# shield.net
KiCad netlist of a schematic drawn in EAGLE
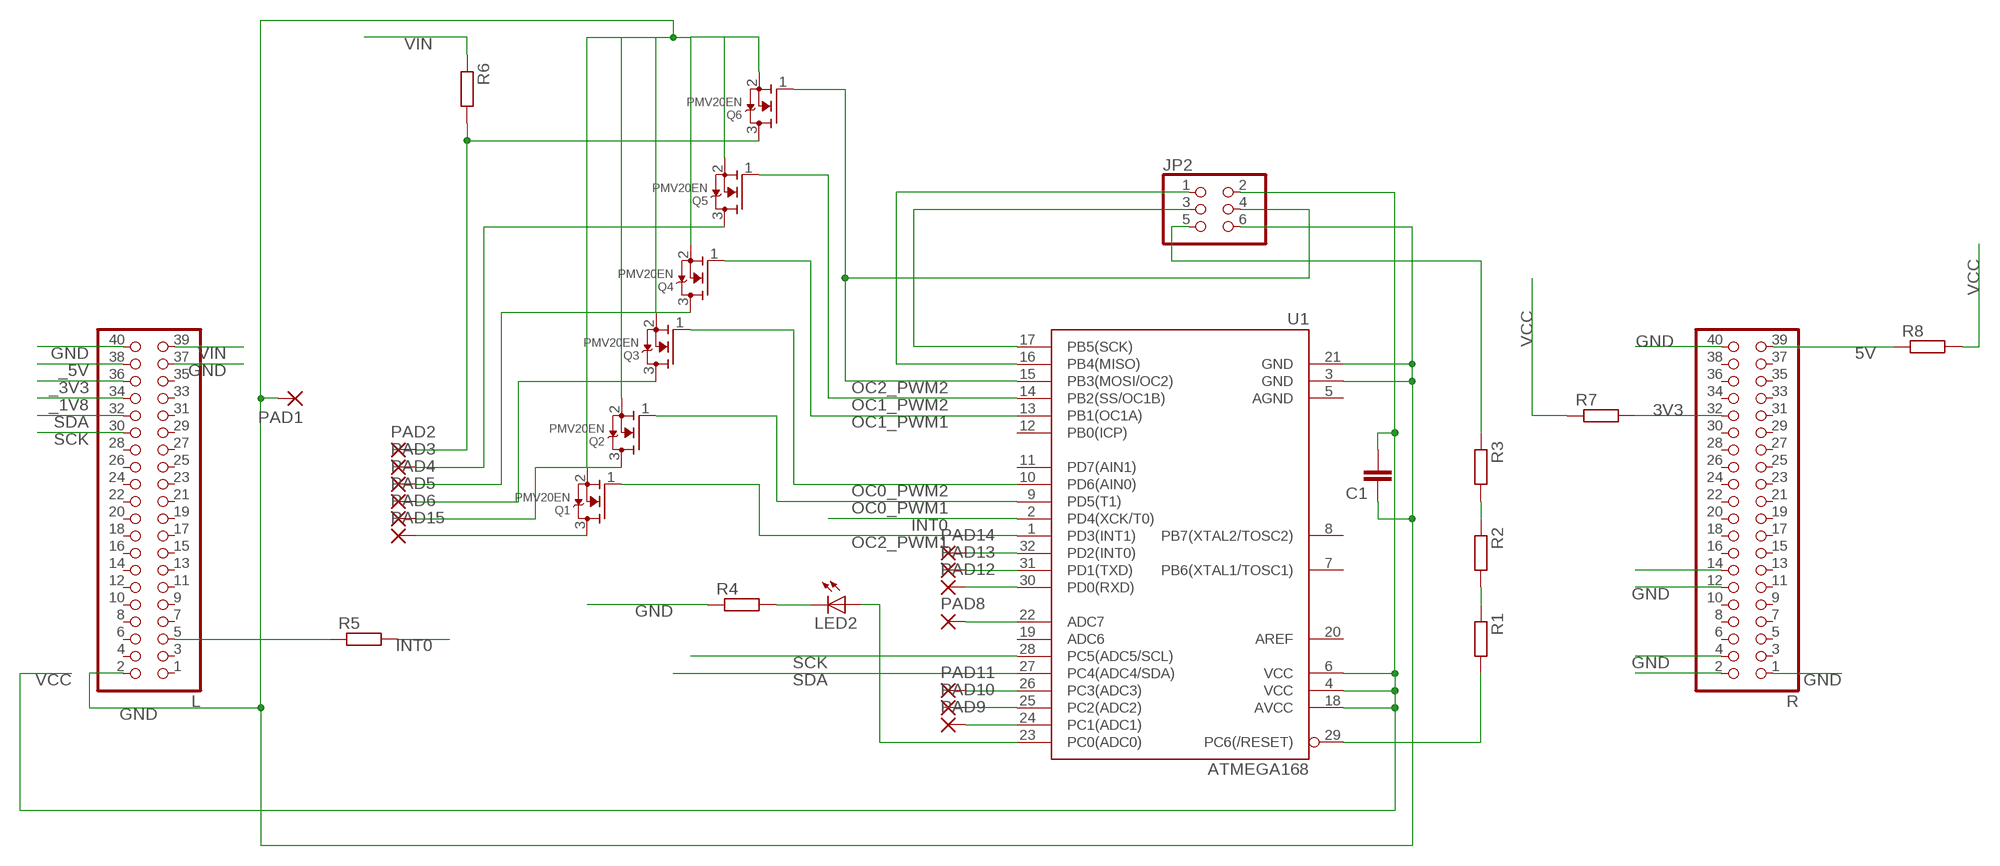
[diagram p0: schematic, sheet 1]

(export (version "E")
  (design (tool "Eeschema 10.0.6"))
  (components
    (comp (ref "C1")
      (value "C-EUC0805")
      (footprint "eagle-import:C0805")
      (libsource (lib "eagle-import") (part "C-EUC0805"))
    )
    (comp (ref "JP2")
      (value "PINHD-2X3")
      (footprint "eagle-import:2X03")
      (libsource (lib "eagle-import") (part "PINHD-2X3"))
    )
    (comp (ref "L")
      (value "PINHD-2X20")
      (footprint "eagle-import:2X20")
      (libsource (lib "eagle-import") (part "PINHD-2X20"))
    )
    (comp (ref "LED2")
      (value "LEDCHIP-LED0805")
      (footprint "eagle-import:CHIP-LED0805")
      (libsource (lib "eagle-import") (part "LEDCHIP-LED0805"))
    )
    (comp (ref "PAD1")
      (value "2,54/0,9")
      (footprint "eagle-import:2,54_0,9")
      (libsource (lib "eagle-import") (part "2,54/0,9"))
    )
    (comp (ref "PAD2")
      (value "2,54/0,9")
      (footprint "eagle-import:2,54_0,9")
      (libsource (lib "eagle-import") (part "2,54/0,9"))
    )
    (comp (ref "PAD3")
      (value "2,54/0,9")
      (footprint "eagle-import:2,54_0,9")
      (libsource (lib "eagle-import") (part "2,54/0,9"))
    )
    (comp (ref "PAD4")
      (value "2,54/0,9")
      (footprint "eagle-import:2,54_0,9")
      (libsource (lib "eagle-import") (part "2,54/0,9"))
    )
    (comp (ref "PAD5")
      (value "2,54/0,9")
      (footprint "eagle-import:2,54_0,9")
      (libsource (lib "eagle-import") (part "2,54/0,9"))
    )
    (comp (ref "PAD6")
      (value "2,54/0,9")
      (footprint "eagle-import:2,54_0,9")
      (libsource (lib "eagle-import") (part "2,54/0,9"))
    )
    (comp (ref "PAD8")
      (value "2,54/0,9")
      (footprint "eagle-import:2,54_0,9")
      (libsource (lib "eagle-import") (part "2,54/0,9"))
    )
    (comp (ref "PAD9")
      (value "2,54/0,9")
      (footprint "eagle-import:2,54_0,9")
      (libsource (lib "eagle-import") (part "2,54/0,9"))
    )
    (comp (ref "PAD10")
      (value "2,54/0,9")
      (footprint "eagle-import:2,54_0,9")
      (libsource (lib "eagle-import") (part "2,54/0,9"))
    )
    (comp (ref "PAD11")
      (value "2,54/0,9")
      (footprint "eagle-import:2,54_0,9")
      (libsource (lib "eagle-import") (part "2,54/0,9"))
    )
    (comp (ref "PAD12")
      (value "2,54/0,9")
      (footprint "eagle-import:2,54_0,9")
      (libsource (lib "eagle-import") (part "2,54/0,9"))
    )
    (comp (ref "PAD13")
      (value "2,54/0,9")
      (footprint "eagle-import:2,54_0,9")
      (libsource (lib "eagle-import") (part "2,54/0,9"))
    )
    (comp (ref "PAD14")
      (value "2,54/0,9")
      (footprint "eagle-import:2,54_0,9")
      (libsource (lib "eagle-import") (part "2,54/0,9"))
    )
    (comp (ref "PAD15")
      (value "2,54/0,9")
      (footprint "eagle-import:2,54_0,9")
      (libsource (lib "eagle-import") (part "2,54/0,9"))
    )
    (comp (ref "Q1")
      (value "PMV20EN")
      (footprint "eagle-import:SOT23")
      (libsource (lib "eagle-import") (part "MOSFET-NREFLOW"))
    )
    (comp (ref "Q2")
      (value "PMV20EN")
      (footprint "eagle-import:SOT23")
      (libsource (lib "eagle-import") (part "MOSFET-NREFLOW"))
    )
    (comp (ref "Q3")
      (value "PMV20EN")
      (footprint "eagle-import:SOT23")
      (libsource (lib "eagle-import") (part "MOSFET-NREFLOW"))
    )
    (comp (ref "Q4")
      (value "PMV20EN")
      (footprint "eagle-import:SOT23")
      (libsource (lib "eagle-import") (part "MOSFET-NREFLOW"))
    )
    (comp (ref "Q5")
      (value "PMV20EN")
      (footprint "eagle-import:SOT23")
      (libsource (lib "eagle-import") (part "MOSFET-NREFLOW"))
    )
    (comp (ref "Q6")
      (value "PMV20EN")
      (footprint "eagle-import:SOT23")
      (libsource (lib "eagle-import") (part "MOSFET-NREFLOW"))
    )
    (comp (ref "R")
      (value "PINHD-2X20")
      (footprint "eagle-import:2X20")
      (libsource (lib "eagle-import") (part "PINHD-2X20"))
    )
    (comp (ref "R1")
      (value "R-EU_M1206")
      (footprint "eagle-import:M1206")
      (libsource (lib "eagle-import") (part "R-EU_M1206"))
    )
    (comp (ref "R2")
      (value "R-EU_M1206")
      (footprint "eagle-import:M1206")
      (libsource (lib "eagle-import") (part "R-EU_M1206"))
    )
    (comp (ref "R3")
      (value "R-EU_M1206")
      (footprint "eagle-import:M1206")
      (libsource (lib "eagle-import") (part "R-EU_M1206"))
    )
    (comp (ref "R4")
      (value "R-EU_M1206")
      (footprint "eagle-import:M1206")
      (libsource (lib "eagle-import") (part "R-EU_M1206"))
    )
    (comp (ref "R5")
      (value "R-EU_M1206")
      (footprint "eagle-import:M1206")
      (libsource (lib "eagle-import") (part "R-EU_M1206"))
    )
    (comp (ref "R6")
      (value "R-EU_M1206")
      (footprint "eagle-import:M1206")
      (libsource (lib "eagle-import") (part "R-EU_M1206"))
    )
    (comp (ref "R7")
      (value "R-EU_M0805")
      (footprint "eagle-import:M0805")
      (libsource (lib "eagle-import") (part "R-EU_M0805"))
    )
    (comp (ref "R8")
      (value "R-EU_M0805")
      (footprint "eagle-import:M0805")
      (libsource (lib "eagle-import") (part "R-EU_M0805"))
    )
    (comp (ref "U1")
      (value "ATMEGA168")
      (footprint "eagle-import:TQFP32-08")
      (libsource (lib "eagle-import") (part "ATMEGA168"))
    )
  )
  (nets
    (net (code "1") (name "/3V3") (class "Default")
      (node (ref "R") (pin "32") (pinfunction "32_32") (pintype "passive"))
      (node (ref "R7") (pin "2") (pinfunction "2_2") (pintype "passive"))
    )
    (net (code "2") (name "/5V") (class "Default")
      (node (ref "R") (pin "39") (pinfunction "39_39") (pintype "passive"))
      (node (ref "R8") (pin "1") (pinfunction "1_1") (pintype "passive"))
    )
    (net (code "3") (name "/GND") (class "Default")
      (node (ref "C1") (pin "1") (pinfunction "1_1") (pintype "passive"))
      (node (ref "JP2") (pin "6") (pinfunction "6_6") (pintype "passive"))
      (node (ref "L") (pin "2") (pinfunction "2_2") (pintype "passive"))
      (node (ref "L") (pin "37") (pinfunction "37_37") (pintype "passive"))
      (node (ref "L") (pin "40") (pinfunction "40_40") (pintype "passive"))
      (node (ref "PAD1") (pin "1") (pinfunction "P_1") (pintype "passive"))
      (node (ref "Q1") (pin "2") (pinfunction "S_2") (pintype "bidirectional"))
      (node (ref "Q2") (pin "2") (pinfunction "S_2") (pintype "bidirectional"))
      (node (ref "Q3") (pin "2") (pinfunction "S_2") (pintype "bidirectional"))
      (node (ref "Q4") (pin "2") (pinfunction "S_2") (pintype "bidirectional"))
      (node (ref "Q5") (pin "2") (pinfunction "S_2") (pintype "bidirectional"))
      (node (ref "Q6") (pin "2") (pinfunction "S_2") (pintype "bidirectional"))
      (node (ref "R") (pin "1") (pinfunction "1_1") (pintype "passive"))
      (node (ref "R") (pin "12") (pinfunction "12_12") (pintype "passive"))
      (node (ref "R") (pin "4") (pinfunction "4_4") (pintype "passive"))
      (node (ref "R") (pin "40") (pinfunction "40_40") (pintype "passive"))
      (node (ref "R4") (pin "1") (pinfunction "1_1") (pintype "passive"))
      (node (ref "U1") (pin "21") (pinfunction "GND_21") (pintype "bidirectional"))
      (node (ref "U1") (pin "3") (pinfunction "GND_3") (pintype "bidirectional"))
    )
    (net (code "4") (name "/INT0") (class "Default")
      (node (ref "R5") (pin "2") (pinfunction "2_2") (pintype "passive"))
      (node (ref "U1") (pin "2") (pinfunction "PD4(XCK/T0)_2") (pintype "bidirectional"))
    )
    (net (code "5") (name "/OC0_PWM1") (class "Default")
      (node (ref "Q2") (pin "1") (pinfunction "G_1") (pintype "bidirectional"))
      (node (ref "U1") (pin "9") (pinfunction "PD5(T1)_9") (pintype "bidirectional"))
    )
    (net (code "6") (name "/OC0_PWM2") (class "Default")
      (node (ref "Q3") (pin "1") (pinfunction "G_1") (pintype "bidirectional"))
      (node (ref "U1") (pin "10") (pinfunction "PD6(AIN0)_10") (pintype "bidirectional"))
    )
    (net (code "7") (name "/OC1_PWM1") (class "Default")
      (node (ref "Q4") (pin "1") (pinfunction "G_1") (pintype "bidirectional"))
      (node (ref "U1") (pin "13") (pinfunction "PB1(OC1A)_13") (pintype "bidirectional"))
    )
    (net (code "8") (name "/OC1_PWM2") (class "Default")
      (node (ref "Q5") (pin "1") (pinfunction "G_1") (pintype "bidirectional"))
      (node (ref "U1") (pin "14") (pinfunction "PB2(SS/OC1B)_14") (pintype "bidirectional"))
    )
    (net (code "9") (name "/OC2_PWM1") (class "Default")
      (node (ref "Q1") (pin "1") (pinfunction "G_1") (pintype "bidirectional"))
      (node (ref "U1") (pin "1") (pinfunction "PD3(INT1)_1") (pintype "bidirectional"))
    )
    (net (code "10") (name "/OC2_PWM2") (class "Default")
      (node (ref "JP2") (pin "4") (pinfunction "4_4") (pintype "passive"))
      (node (ref "Q6") (pin "1") (pinfunction "G_1") (pintype "bidirectional"))
      (node (ref "U1") (pin "15") (pinfunction "PB3(MOSI/OC2)_15") (pintype "bidirectional"))
    )
    (net (code "11") (name "/SCK") (class "Default")
      (node (ref "L") (pin "30") (pinfunction "30_30") (pintype "passive"))
      (node (ref "U1") (pin "28") (pinfunction "PC5(ADC5/SCL)_28") (pintype "bidirectional"))
    )
    (net (code "12") (name "/SDA") (class "Default")
      (node (ref "L") (pin "32") (pinfunction "32_32") (pintype "passive"))
      (node (ref "U1") (pin "27") (pinfunction "PC4(ADC4/SDA)_27") (pintype "bidirectional"))
    )
    (net (code "13") (name "/VCC") (class "Default")
      (node (ref "C1") (pin "2") (pinfunction "2_2") (pintype "passive"))
      (node (ref "JP2") (pin "2") (pinfunction "2_2") (pintype "passive"))
      (node (ref "R7") (pin "1") (pinfunction "1_1") (pintype "passive"))
      (node (ref "R8") (pin "2") (pinfunction "2_2") (pintype "passive"))
      (node (ref "U1") (pin "18") (pinfunction "AVCC_18") (pintype "bidirectional"))
      (node (ref "U1") (pin "4") (pinfunction "VCC_4") (pintype "bidirectional"))
      (node (ref "U1") (pin "6") (pinfunction "VCC_6") (pintype "bidirectional"))
    )
    (net (code "14") (name "/VIN") (class "Default")
      (node (ref "L") (pin "39") (pinfunction "39_39") (pintype "passive"))
      (node (ref "R6") (pin "1") (pinfunction "1_1") (pintype "passive"))
    )
    (net (code "15") (name "/_1V8") (class "Default")
      (node (ref "L") (pin "34") (pinfunction "34_34") (pintype "passive"))
    )
    (net (code "16") (name "/_3V3") (class "Default")
      (node (ref "L") (pin "36") (pinfunction "36_36") (pintype "passive"))
    )
    (net (code "17") (name "/_5V") (class "Default")
      (node (ref "L") (pin "38") (pinfunction "38_38") (pintype "passive"))
    )
    (net (code "18") (name "Net-(JP2-Pad5)") (class "Default")
      (node (ref "JP2") (pin "5") (pinfunction "5_5") (pintype "passive"))
      (node (ref "R3") (pin "1") (pinfunction "1_1") (pintype "passive"))
    )
    (net (code "19") (name "Net-(L-Pad5)") (class "Default")
      (node (ref "L") (pin "5") (pinfunction "5_5") (pintype "passive"))
      (node (ref "R5") (pin "1") (pinfunction "1_1") (pintype "passive"))
    )
    (net (code "20") (name "Net-(LED2-PadC)") (class "Default")
      (node (ref "LED2") (pin "C") (pinfunction "C_C") (pintype "passive"))
      (node (ref "R4") (pin "2") (pinfunction "2_2") (pintype "passive"))
    )
    (net (code "21") (name "Net-(PAD2-P)") (class "Default")
      (node (ref "PAD2") (pin "1") (pinfunction "P_1") (pintype "passive"))
      (node (ref "Q6") (pin "3") (pinfunction "D_3") (pintype "bidirectional"))
      (node (ref "R6") (pin "2") (pinfunction "2_2") (pintype "passive"))
    )
    (net (code "22") (name "Net-(PAD3-P)") (class "Default")
      (node (ref "PAD3") (pin "1") (pinfunction "P_1") (pintype "passive"))
      (node (ref "Q5") (pin "3") (pinfunction "D_3") (pintype "bidirectional"))
    )
    (net (code "23") (name "Net-(PAD4-P)") (class "Default")
      (node (ref "PAD4") (pin "1") (pinfunction "P_1") (pintype "passive"))
      (node (ref "Q4") (pin "3") (pinfunction "D_3") (pintype "bidirectional"))
    )
    (net (code "24") (name "Net-(PAD5-P)") (class "Default")
      (node (ref "PAD5") (pin "1") (pinfunction "P_1") (pintype "passive"))
      (node (ref "Q3") (pin "3") (pinfunction "D_3") (pintype "bidirectional"))
    )
    (net (code "25") (name "Net-(PAD6-P)") (class "Default")
      (node (ref "PAD6") (pin "1") (pinfunction "P_1") (pintype "passive"))
      (node (ref "Q2") (pin "3") (pinfunction "D_3") (pintype "bidirectional"))
    )
    (net (code "26") (name "Net-(PAD8-P)") (class "Default")
      (node (ref "PAD8") (pin "1") (pinfunction "P_1") (pintype "passive"))
      (node (ref "U1") (pin "22") (pinfunction "ADC7_22") (pintype "bidirectional"))
    )
    (net (code "27") (name "Net-(PAD9-P)") (class "Default")
      (node (ref "PAD9") (pin "1") (pinfunction "P_1") (pintype "passive"))
      (node (ref "U1") (pin "24") (pinfunction "PC1(ADC1)_24") (pintype "bidirectional"))
    )
    (net (code "28") (name "Net-(PAD10-P)") (class "Default")
      (node (ref "PAD10") (pin "1") (pinfunction "P_1") (pintype "passive"))
      (node (ref "U1") (pin "25") (pinfunction "PC2(ADC2)_25") (pintype "bidirectional"))
    )
    (net (code "29") (name "Net-(PAD11-P)") (class "Default")
      (node (ref "PAD11") (pin "1") (pinfunction "P_1") (pintype "passive"))
      (node (ref "U1") (pin "26") (pinfunction "PC3(ADC3)_26") (pintype "bidirectional"))
    )
    (net (code "30") (name "Net-(PAD12-P)") (class "Default")
      (node (ref "PAD12") (pin "1") (pinfunction "P_1") (pintype "passive"))
      (node (ref "U1") (pin "30") (pinfunction "PD0(RXD)_30") (pintype "bidirectional"))
    )
    (net (code "31") (name "Net-(PAD13-P)") (class "Default")
      (node (ref "PAD13") (pin "1") (pinfunction "P_1") (pintype "passive"))
      (node (ref "U1") (pin "31") (pinfunction "PD1(TXD)_31") (pintype "bidirectional"))
    )
    (net (code "32") (name "Net-(PAD14-P)") (class "Default")
      (node (ref "PAD14") (pin "1") (pinfunction "P_1") (pintype "passive"))
      (node (ref "U1") (pin "32") (pinfunction "PD2(INT0)_32") (pintype "bidirectional"))
    )
    (net (code "33") (name "Net-(PAD15-P)") (class "Default")
      (node (ref "PAD15") (pin "1") (pinfunction "P_1") (pintype "passive"))
      (node (ref "Q1") (pin "3") (pinfunction "D_3") (pintype "bidirectional"))
    )
    (net (code "34") (name "Net-(R1-Pad1)") (class "Default")
      (node (ref "R1") (pin "1") (pinfunction "1_1") (pintype "passive"))
      (node (ref "R2") (pin "2") (pinfunction "2_2") (pintype "passive"))
    )
    (net (code "35") (name "Net-(R2-Pad1)") (class "Default")
      (node (ref "R2") (pin "1") (pinfunction "1_1") (pintype "passive"))
      (node (ref "R3") (pin "2") (pinfunction "2_2") (pintype "passive"))
    )
    (net (code "36") (name "Net-(U1-PB4(MISO))") (class "Default")
      (node (ref "JP2") (pin "1") (pinfunction "1_1") (pintype "passive"))
      (node (ref "U1") (pin "16") (pinfunction "PB4(MISO)_16") (pintype "bidirectional"))
    )
    (net (code "37") (name "Net-(U1-PB5(SCK))") (class "Default")
      (node (ref "JP2") (pin "3") (pinfunction "3_3") (pintype "passive"))
      (node (ref "U1") (pin "17") (pinfunction "PB5(SCK)_17") (pintype "bidirectional"))
    )
    (net (code "38") (name "Net-(U1-PC0(ADC0))") (class "Default")
      (node (ref "LED2") (pin "A") (pinfunction "A_A") (pintype "passive"))
      (node (ref "U1") (pin "23") (pinfunction "PC0(ADC0)_23") (pintype "bidirectional"))
    )
    (net (code "39") (name "Net-(U1-PC6({slash}RESET))") (class "Default")
      (node (ref "R1") (pin "2") (pinfunction "2_2") (pintype "passive"))
      (node (ref "U1") (pin "29") (pinfunction "PC6(/RESET)_29") (pintype "bidirectional"))
    )
    (net (code "40") (name "unconnected-(L-Pad1)") (class "Default")
      (node (ref "L") (pin "1") (pinfunction "1_1") (pintype "passive"))
    )
    (net (code "41") (name "unconnected-(L-Pad3)") (class "Default")
      (node (ref "L") (pin "3") (pinfunction "3_3") (pintype "passive"))
    )
    (net (code "42") (name "unconnected-(L-Pad4)") (class "Default")
      (node (ref "L") (pin "4") (pinfunction "4_4") (pintype "passive"))
    )
    (net (code "43") (name "unconnected-(L-Pad6)") (class "Default")
      (node (ref "L") (pin "6") (pinfunction "6_6") (pintype "passive"))
    )
    (net (code "44") (name "unconnected-(L-Pad7)") (class "Default")
      (node (ref "L") (pin "7") (pinfunction "7_7") (pintype "passive"))
    )
    (net (code "45") (name "unconnected-(L-Pad8)") (class "Default")
      (node (ref "L") (pin "8") (pinfunction "8_8") (pintype "passive"))
    )
    (net (code "46") (name "unconnected-(L-Pad9)") (class "Default")
      (node (ref "L") (pin "9") (pinfunction "9_9") (pintype "passive"))
    )
    (net (code "47") (name "unconnected-(L-Pad10)") (class "Default")
      (node (ref "L") (pin "10") (pinfunction "10_10") (pintype "passive"))
    )
    (net (code "48") (name "unconnected-(L-Pad11)") (class "Default")
      (node (ref "L") (pin "11") (pinfunction "11_11") (pintype "passive"))
    )
    (net (code "49") (name "unconnected-(L-Pad12)") (class "Default")
      (node (ref "L") (pin "12") (pinfunction "12_12") (pintype "passive"))
    )
    (net (code "50") (name "unconnected-(L-Pad13)") (class "Default")
      (node (ref "L") (pin "13") (pinfunction "13_13") (pintype "passive"))
    )
    (net (code "51") (name "unconnected-(L-Pad14)") (class "Default")
      (node (ref "L") (pin "14") (pinfunction "14_14") (pintype "passive"))
    )
    (net (code "52") (name "unconnected-(L-Pad15)") (class "Default")
      (node (ref "L") (pin "15") (pinfunction "15_15") (pintype "passive"))
    )
    (net (code "53") (name "unconnected-(L-Pad16)") (class "Default")
      (node (ref "L") (pin "16") (pinfunction "16_16") (pintype "passive"))
    )
    (net (code "54") (name "unconnected-(L-Pad17)") (class "Default")
      (node (ref "L") (pin "17") (pinfunction "17_17") (pintype "passive"))
    )
    (net (code "55") (name "unconnected-(L-Pad18)") (class "Default")
      (node (ref "L") (pin "18") (pinfunction "18_18") (pintype "passive"))
    )
    (net (code "56") (name "unconnected-(L-Pad19)") (class "Default")
      (node (ref "L") (pin "19") (pinfunction "19_19") (pintype "passive"))
    )
    (net (code "57") (name "unconnected-(L-Pad20)") (class "Default")
      (node (ref "L") (pin "20") (pinfunction "20_20") (pintype "passive"))
    )
    (net (code "58") (name "unconnected-(L-Pad21)") (class "Default")
      (node (ref "L") (pin "21") (pinfunction "21_21") (pintype "passive"))
    )
    (net (code "59") (name "unconnected-(L-Pad22)") (class "Default")
      (node (ref "L") (pin "22") (pinfunction "22_22") (pintype "passive"))
    )
    (net (code "60") (name "unconnected-(L-Pad23)") (class "Default")
      (node (ref "L") (pin "23") (pinfunction "23_23") (pintype "passive"))
    )
    (net (code "61") (name "unconnected-(L-Pad24)") (class "Default")
      (node (ref "L") (pin "24") (pinfunction "24_24") (pintype "passive"))
    )
    (net (code "62") (name "unconnected-(L-Pad25)") (class "Default")
      (node (ref "L") (pin "25") (pinfunction "25_25") (pintype "passive"))
    )
    (net (code "63") (name "unconnected-(L-Pad26)") (class "Default")
      (node (ref "L") (pin "26") (pinfunction "26_26") (pintype "passive"))
    )
    (net (code "64") (name "unconnected-(L-Pad27)") (class "Default")
      (node (ref "L") (pin "27") (pinfunction "27_27") (pintype "passive"))
    )
    (net (code "65") (name "unconnected-(L-Pad28)") (class "Default")
      (node (ref "L") (pin "28") (pinfunction "28_28") (pintype "passive"))
    )
    (net (code "66") (name "unconnected-(L-Pad29)") (class "Default")
      (node (ref "L") (pin "29") (pinfunction "29_29") (pintype "passive"))
    )
    (net (code "67") (name "unconnected-(L-Pad31)") (class "Default")
      (node (ref "L") (pin "31") (pinfunction "31_31") (pintype "passive"))
    )
    (net (code "68") (name "unconnected-(L-Pad33)") (class "Default")
      (node (ref "L") (pin "33") (pinfunction "33_33") (pintype "passive"))
    )
    (net (code "69") (name "unconnected-(L-Pad35)") (class "Default")
      (node (ref "L") (pin "35") (pinfunction "35_35") (pintype "passive"))
    )
    (net (code "70") (name "unconnected-(R-Pad2)") (class "Default")
      (node (ref "R") (pin "2") (pinfunction "2_2") (pintype "passive"))
    )
    (net (code "71") (name "unconnected-(R-Pad3)") (class "Default")
      (node (ref "R") (pin "3") (pinfunction "3_3") (pintype "passive"))
    )
    (net (code "72") (name "unconnected-(R-Pad5)") (class "Default")
      (node (ref "R") (pin "5") (pinfunction "5_5") (pintype "passive"))
    )
    (net (code "73") (name "unconnected-(R-Pad6)") (class "Default")
      (node (ref "R") (pin "6") (pinfunction "6_6") (pintype "passive"))
    )
    (net (code "74") (name "unconnected-(R-Pad7)") (class "Default")
      (node (ref "R") (pin "7") (pinfunction "7_7") (pintype "passive"))
    )
    (net (code "75") (name "unconnected-(R-Pad8)") (class "Default")
      (node (ref "R") (pin "8") (pinfunction "8_8") (pintype "passive"))
    )
    (net (code "76") (name "unconnected-(R-Pad9)") (class "Default")
      (node (ref "R") (pin "9") (pinfunction "9_9") (pintype "passive"))
    )
    (net (code "77") (name "unconnected-(R-Pad10)") (class "Default")
      (node (ref "R") (pin "10") (pinfunction "10_10") (pintype "passive"))
    )
    (net (code "78") (name "unconnected-(R-Pad11)") (class "Default")
      (node (ref "R") (pin "11") (pinfunction "11_11") (pintype "passive"))
    )
    (net (code "79") (name "unconnected-(R-Pad13)") (class "Default")
      (node (ref "R") (pin "13") (pinfunction "13_13") (pintype "passive"))
    )
    (net (code "80") (name "unconnected-(R-Pad14)") (class "Default")
      (node (ref "R") (pin "14") (pinfunction "14_14") (pintype "passive"))
    )
    (net (code "81") (name "unconnected-(R-Pad15)") (class "Default")
      (node (ref "R") (pin "15") (pinfunction "15_15") (pintype "passive"))
    )
    (net (code "82") (name "unconnected-(R-Pad16)") (class "Default")
      (node (ref "R") (pin "16") (pinfunction "16_16") (pintype "passive"))
    )
    (net (code "83") (name "unconnected-(R-Pad17)") (class "Default")
      (node (ref "R") (pin "17") (pinfunction "17_17") (pintype "passive"))
    )
    (net (code "84") (name "unconnected-(R-Pad18)") (class "Default")
      (node (ref "R") (pin "18") (pinfunction "18_18") (pintype "passive"))
    )
    (net (code "85") (name "unconnected-(R-Pad19)") (class "Default")
      (node (ref "R") (pin "19") (pinfunction "19_19") (pintype "passive"))
    )
    (net (code "86") (name "unconnected-(R-Pad20)") (class "Default")
      (node (ref "R") (pin "20") (pinfunction "20_20") (pintype "passive"))
    )
    (net (code "87") (name "unconnected-(R-Pad21)") (class "Default")
      (node (ref "R") (pin "21") (pinfunction "21_21") (pintype "passive"))
    )
    (net (code "88") (name "unconnected-(R-Pad22)") (class "Default")
      (node (ref "R") (pin "22") (pinfunction "22_22") (pintype "passive"))
    )
    (net (code "89") (name "unconnected-(R-Pad23)") (class "Default")
      (node (ref "R") (pin "23") (pinfunction "23_23") (pintype "passive"))
    )
    (net (code "90") (name "unconnected-(R-Pad24)") (class "Default")
      (node (ref "R") (pin "24") (pinfunction "24_24") (pintype "passive"))
    )
    (net (code "91") (name "unconnected-(R-Pad25)") (class "Default")
      (node (ref "R") (pin "25") (pinfunction "25_25") (pintype "passive"))
    )
    (net (code "92") (name "unconnected-(R-Pad26)") (class "Default")
      (node (ref "R") (pin "26") (pinfunction "26_26") (pintype "passive"))
    )
    (net (code "93") (name "unconnected-(R-Pad27)") (class "Default")
      (node (ref "R") (pin "27") (pinfunction "27_27") (pintype "passive"))
    )
    (net (code "94") (name "unconnected-(R-Pad28)") (class "Default")
      (node (ref "R") (pin "28") (pinfunction "28_28") (pintype "passive"))
    )
    (net (code "95") (name "unconnected-(R-Pad29)") (class "Default")
      (node (ref "R") (pin "29") (pinfunction "29_29") (pintype "passive"))
    )
    (net (code "96") (name "unconnected-(R-Pad30)") (class "Default")
      (node (ref "R") (pin "30") (pinfunction "30_30") (pintype "passive"))
    )
    (net (code "97") (name "unconnected-(R-Pad31)") (class "Default")
      (node (ref "R") (pin "31") (pinfunction "31_31") (pintype "passive"))
    )
    (net (code "98") (name "unconnected-(R-Pad33)") (class "Default")
      (node (ref "R") (pin "33") (pinfunction "33_33") (pintype "passive"))
    )
    (net (code "99") (name "unconnected-(R-Pad34)") (class "Default")
      (node (ref "R") (pin "34") (pinfunction "34_34") (pintype "passive"))
    )
    (net (code "100") (name "unconnected-(R-Pad35)") (class "Default")
      (node (ref "R") (pin "35") (pinfunction "35_35") (pintype "passive"))
    )
    (net (code "101") (name "unconnected-(R-Pad36)") (class "Default")
      (node (ref "R") (pin "36") (pinfunction "36_36") (pintype "passive"))
    )
    (net (code "102") (name "unconnected-(R-Pad37)") (class "Default")
      (node (ref "R") (pin "37") (pinfunction "37_37") (pintype "passive"))
    )
    (net (code "103") (name "unconnected-(R-Pad38)") (class "Default")
      (node (ref "R") (pin "38") (pinfunction "38_38") (pintype "passive"))
    )
    (net (code "104") (name "unconnected-(U1-ADC6-Pad19)") (class "Default")
      (node (ref "U1") (pin "19") (pinfunction "ADC6_19") (pintype "bidirectional"))
    )
    (net (code "105") (name "unconnected-(U1-AGND-Pad5)") (class "Default")
      (node (ref "U1") (pin "5") (pinfunction "AGND_5") (pintype "bidirectional"))
    )
    (net (code "106") (name "unconnected-(U1-AREF-Pad20)") (class "Default")
      (node (ref "U1") (pin "20") (pinfunction "AREF_20") (pintype "bidirectional"))
    )
    (net (code "107") (name "unconnected-(U1-PB0(ICP)-Pad12)") (class "Default")
      (node (ref "U1") (pin "12") (pinfunction "PB0(ICP)_12") (pintype "bidirectional"))
    )
    (net (code "108") (name "unconnected-(U1-PB6(XTAL1{slash}TOSC1)-Pad7)") (class "Default")
      (node (ref "U1") (pin "7") (pinfunction "PB6(XTAL1/TOSC1)_7") (pintype "bidirectional"))
    )
    (net (code "109") (name "unconnected-(U1-PB7(XTAL2{slash}TOSC2)-Pad8)") (class "Default")
      (node (ref "U1") (pin "8") (pinfunction "PB7(XTAL2/TOSC2)_8") (pintype "bidirectional"))
    )
    (net (code "110") (name "unconnected-(U1-PD7(AIN1)-Pad11)") (class "Default")
      (node (ref "U1") (pin "11") (pinfunction "PD7(AIN1)_11") (pintype "bidirectional"))
    )
  )
)
